# 06_POWER_5.net
KiCad netlist of a schematic drawn in Altium Designer
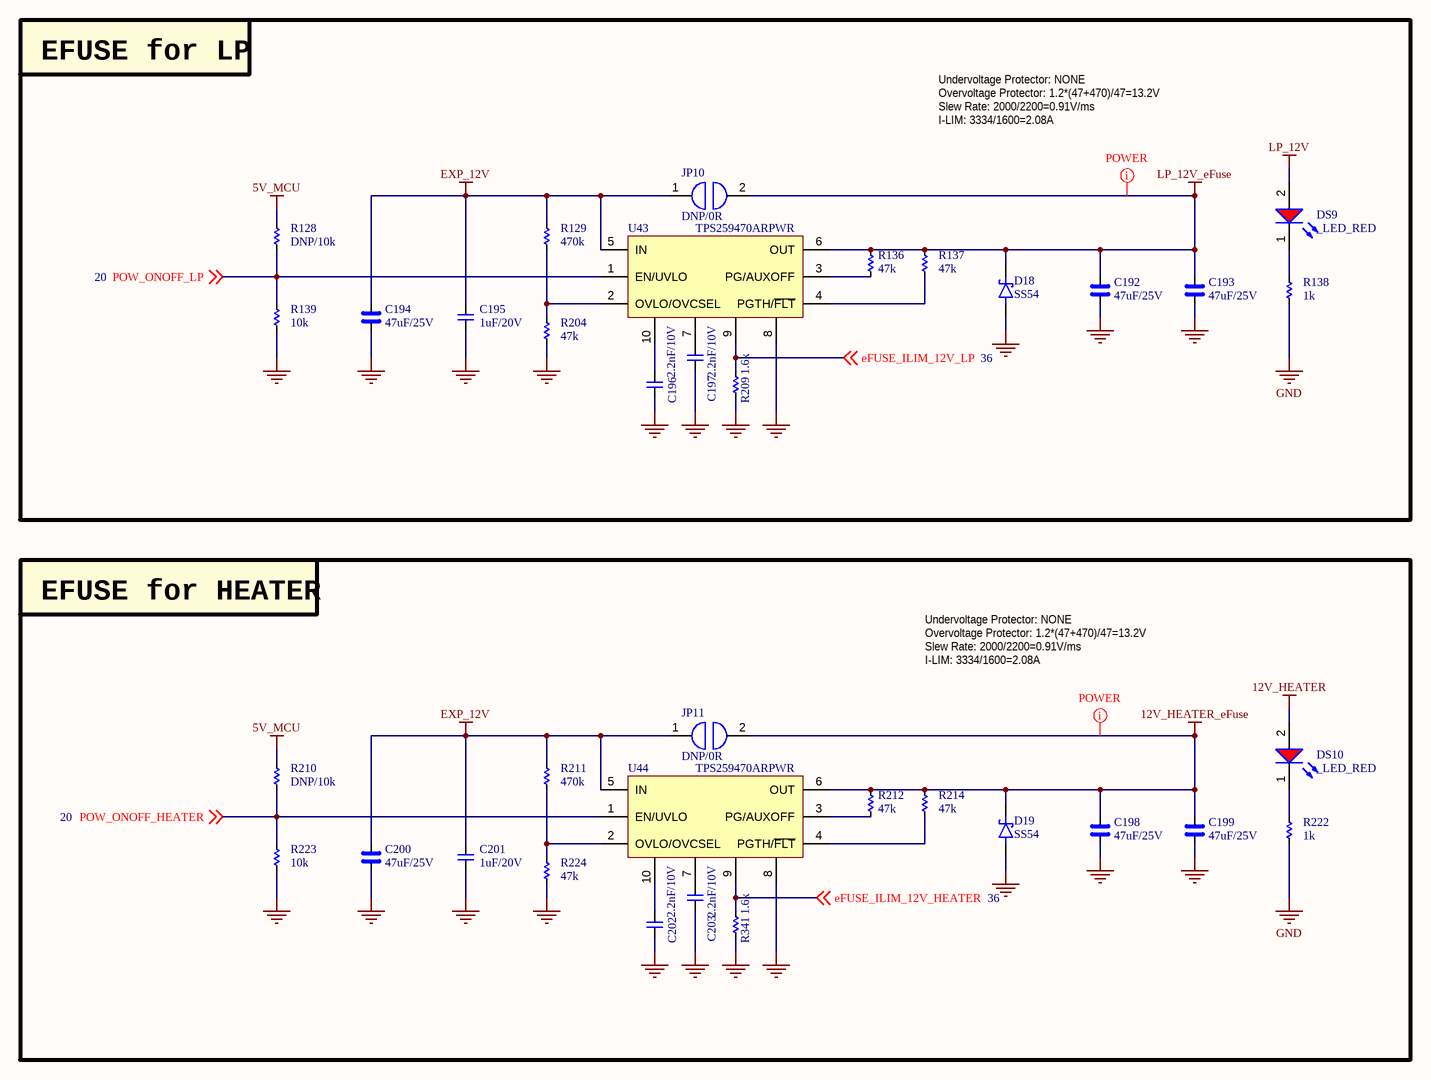
[diagram p0: 06_POWER_5.SchDoc]

(export (version "E")
  (design (tool "Eeschema 10.0.6"))
  (components
    (comp (ref "C192")
      (value "47uF/25V")
      (footprint "CAP_C_3225X80")
      (description "CAP High Value")
      (libsource (lib "LABLIB") (part "_CAP_C_High_2"))
    )
    (comp (ref "C193")
      (value "47uF/25V")
      (footprint "CAP_C_3225X80")
      (description "CAP High Value")
      (libsource (lib "LABLIB") (part "_CAP_C_High_2"))
    )
    (comp (ref "C194")
      (value "47uF/25V")
      (footprint "CAP_C_3225X80")
      (description "CAP High Value")
      (libsource (lib "LABLIB") (part "_CAP_C_High_2"))
    )
    (comp (ref "C195")
      (value "1uF/20V")
      (footprint "CAP_C_1005X60")
      (description "CAP")
      (libsource (lib "LABLIB") (part "_CAP_C_2"))
    )
    (comp (ref "C196")
      (value "2.2nF/10V")
      (footprint "CAP_C_1005X60")
      (description "CAP")
      (libsource (lib "LABLIB") (part "_CAP_C_2"))
    )
    (comp (ref "C197")
      (value "2.2nF/10V")
      (footprint "CAP_C_1005X60")
      (description "CAP")
      (libsource (lib "LABLIB") (part "_CAP_C_2"))
    )
    (comp (ref "C198")
      (value "47uF/25V")
      (footprint "CAP_C_3225X80")
      (description "CAP High Value")
      (libsource (lib "LABLIB") (part "_CAP_C_High_2"))
    )
    (comp (ref "C199")
      (value "47uF/25V")
      (footprint "CAP_C_3225X80")
      (description "CAP High Value")
      (libsource (lib "LABLIB") (part "_CAP_C_High_2"))
    )
    (comp (ref "C200")
      (value "47uF/25V")
      (footprint "CAP_C_3225X80")
      (description "CAP High Value")
      (libsource (lib "LABLIB") (part "_CAP_C_High_2"))
    )
    (comp (ref "C201")
      (value "1uF/20V")
      (footprint "CAP_C_1005X60")
      (description "CAP")
      (libsource (lib "LABLIB") (part "_CAP_C_2"))
    )
    (comp (ref "C202")
      (value "2.2nF/10V")
      (footprint "CAP_C_1005X60")
      (description "CAP")
      (libsource (lib "LABLIB") (part "_CAP_C_2"))
    )
    (comp (ref "C203")
      (value "2.2nF/10V")
      (footprint "CAP_C_1005X60")
      (description "CAP")
      (libsource (lib "LABLIB") (part "_CAP_C_2"))
    )
    (comp (ref "D18")
      (value "SS54")
      (footprint "DO-214AC_SMA")
      (description "DIODE SCHOTTKY")
      (libsource (lib "LABLIB") (part "DIODE SCHOTTKY"))
    )
    (comp (ref "D19")
      (value "SS54")
      (footprint "DO-214AC_SMA")
      (description "DIODE SCHOTTKY")
      (libsource (lib "LABLIB") (part "DIODE SCHOTTKY"))
    )
    (comp (ref "DS9") (value "_LED_RED") (footprint "LED_0603") (libsource (lib "LABLIB") (part "_LED_RED")))
    (comp (ref "DS10") (value "_LED_RED") (footprint "LED_0603") (libsource (lib "LABLIB") (part "_LED_RED")))
    (comp (ref "JP10") (value "DNP/0R") (footprint "JUMPER_1608") (libsource (lib "EXP_V1") (part "JUMPER")))
    (comp (ref "JP11") (value "DNP/0R") (footprint "JUMPER_1608") (libsource (lib "EXP_V1") (part "JUMPER")))
    (comp (ref "R128")
      (value "DNP/10k")
      (footprint "RES_C_1005X40")
      (description "RES")
      (libsource (lib "LABLIB") (part "_RES_B_2"))
    )
    (comp (ref "R129")
      (value "470k")
      (footprint "RES_C_1005X40")
      (description "RES")
      (libsource (lib "LABLIB") (part "_RES_B_2"))
    )
    (comp (ref "R136")
      (value "47k")
      (footprint "RES_C_1005X40")
      (description "RES")
      (libsource (lib "LABLIB") (part "_RES_B_2"))
    )
    (comp (ref "R137")
      (value "47k")
      (footprint "RES_C_1005X40")
      (description "RES")
      (libsource (lib "LABLIB") (part "_RES_B_2"))
    )
    (comp (ref "R138")
      (value "1k")
      (footprint "RES_C_1005X40")
      (description "RES")
      (libsource (lib "LABLIB") (part "_RES_B_2"))
    )
    (comp (ref "R139")
      (value "10k")
      (footprint "RES_C_1005X40")
      (description "RES")
      (libsource (lib "LABLIB") (part "_RES_B_2"))
    )
    (comp (ref "R204")
      (value "47k")
      (footprint "RES_C_1005X40")
      (description "RES")
      (libsource (lib "LABLIB") (part "_RES_B_2"))
    )
    (comp (ref "R209")
      (value "1.6k")
      (footprint "RES_C_1005X40")
      (description "RES")
      (libsource (lib "LABLIB") (part "_RES_B_2"))
    )
    (comp (ref "R210")
      (value "DNP/10k")
      (footprint "RES_C_1005X40")
      (description "RES")
      (libsource (lib "LABLIB") (part "_RES_B_2"))
    )
    (comp (ref "R211")
      (value "470k")
      (footprint "RES_C_1005X40")
      (description "RES")
      (libsource (lib "LABLIB") (part "_RES_B_2"))
    )
    (comp (ref "R212")
      (value "47k")
      (footprint "RES_C_1005X40")
      (description "RES")
      (libsource (lib "LABLIB") (part "_RES_B_2"))
    )
    (comp (ref "R214")
      (value "47k")
      (footprint "RES_C_1005X40")
      (description "RES")
      (libsource (lib "LABLIB") (part "_RES_B_2"))
    )
    (comp (ref "R222")
      (value "1k")
      (footprint "RES_C_1005X40")
      (description "RES")
      (libsource (lib "LABLIB") (part "_RES_B_2"))
    )
    (comp (ref "R223")
      (value "10k")
      (footprint "RES_C_1005X40")
      (description "RES")
      (libsource (lib "LABLIB") (part "_RES_B_2"))
    )
    (comp (ref "R224")
      (value "47k")
      (footprint "RES_C_1005X40")
      (description "RES")
      (libsource (lib "LABLIB") (part "_RES_B_2"))
    )
    (comp (ref "R341")
      (value "1.6k")
      (footprint "RES_C_1005X40")
      (description "RES")
      (libsource (lib "LABLIB") (part "_RES_B_2"))
    )
    (comp (ref "U43")
      (value "TPS259470ARPWR")
      (footprint "VQFN-HR-10")
      (libsource (lib "EXP_HW_V3") (part "TPS259470ARPWR"))
    )
    (comp (ref "U44")
      (value "TPS259470ARPWR")
      (footprint "VQFN-HR-10")
      (libsource (lib "EXP_HW_V3") (part "TPS259470ARPWR"))
    )
  )
  (nets
    (net (code "1") (name "5V_MCU") (class "Default")
      (node (ref "R128") (pin "1") (pinfunction "1_1") (pintype "passive"))
      (node (ref "R210") (pin "1") (pinfunction "1_1") (pintype "passive"))
    )
    (net (code "2") (name "12V_HEATER") (class "Default")
      (node (ref "DS10") (pin "2") (pinfunction "A_2") (pintype "passive"))
    )
    (net (code "3") (name "12V_HEATER_eFuse") (class "Default")
      (node (ref "C198") (pin "2") (pinfunction "2_2") (pintype "passive"))
      (node (ref "C199") (pin "2") (pinfunction "2_2") (pintype "passive"))
      (node (ref "D19") (pin "1") (pinfunction "K_1") (pintype "passive"))
      (node (ref "JP11") (pin "2") (pinfunction "2_2") (pintype "passive"))
      (node (ref "R212") (pin "2") (pinfunction "2_2") (pintype "passive"))
      (node (ref "R214") (pin "2") (pinfunction "2_2") (pintype "passive"))
      (node (ref "U44") (pin "6") (pinfunction "OUT_6") (pintype "passive"))
    )
    (net (code "4") (name "EXP_12V") (class "Default")
      (node (ref "C194") (pin "2") (pinfunction "2_2") (pintype "passive"))
      (node (ref "C195") (pin "2") (pinfunction "2_2") (pintype "passive"))
      (node (ref "C200") (pin "2") (pinfunction "2_2") (pintype "passive"))
      (node (ref "C201") (pin "2") (pinfunction "2_2") (pintype "passive"))
      (node (ref "JP10") (pin "1") (pinfunction "1_1") (pintype "passive"))
      (node (ref "JP11") (pin "1") (pinfunction "1_1") (pintype "passive"))
      (node (ref "R129") (pin "2") (pinfunction "2_2") (pintype "passive"))
      (node (ref "R211") (pin "2") (pinfunction "2_2") (pintype "passive"))
      (node (ref "U43") (pin "5") (pinfunction "IN_5") (pintype "passive"))
      (node (ref "U44") (pin "5") (pinfunction "IN_5") (pintype "passive"))
    )
    (net (code "5") (name "GND") (class "Default")
      (node (ref "C192") (pin "1") (pinfunction "1_1") (pintype "passive"))
      (node (ref "C193") (pin "1") (pinfunction "1_1") (pintype "passive"))
      (node (ref "C194") (pin "1") (pinfunction "1_1") (pintype "passive"))
      (node (ref "C195") (pin "1") (pinfunction "1_1") (pintype "passive"))
      (node (ref "C196") (pin "1") (pinfunction "1_1") (pintype "passive"))
      (node (ref "C197") (pin "1") (pinfunction "1_1") (pintype "passive"))
      (node (ref "C198") (pin "1") (pinfunction "1_1") (pintype "passive"))
      (node (ref "C199") (pin "1") (pinfunction "1_1") (pintype "passive"))
      (node (ref "C200") (pin "1") (pinfunction "1_1") (pintype "passive"))
      (node (ref "C201") (pin "1") (pinfunction "1_1") (pintype "passive"))
      (node (ref "C202") (pin "1") (pinfunction "1_1") (pintype "passive"))
      (node (ref "C203") (pin "1") (pinfunction "1_1") (pintype "passive"))
      (node (ref "D18") (pin "2") (pinfunction "A_2") (pintype "passive"))
      (node (ref "D19") (pin "2") (pinfunction "A_2") (pintype "passive"))
      (node (ref "R138") (pin "1") (pinfunction "1_1") (pintype "passive"))
      (node (ref "R139") (pin "2") (pinfunction "2_2") (pintype "passive"))
      (node (ref "R204") (pin "1") (pinfunction "1_1") (pintype "passive"))
      (node (ref "R209") (pin "1") (pinfunction "1_1") (pintype "passive"))
      (node (ref "R222") (pin "1") (pinfunction "1_1") (pintype "passive"))
      (node (ref "R223") (pin "2") (pinfunction "2_2") (pintype "passive"))
      (node (ref "R224") (pin "1") (pinfunction "1_1") (pintype "passive"))
      (node (ref "R341") (pin "1") (pinfunction "1_1") (pintype "passive"))
      (node (ref "U43") (pin "8") (pinfunction "8_8") (pintype "passive"))
      (node (ref "U44") (pin "8") (pinfunction "8_8") (pintype "passive"))
    )
    (net (code "6") (name "LP_12V") (class "Default")
      (node (ref "DS9") (pin "2") (pinfunction "A_2") (pintype "passive"))
    )
    (net (code "7") (name "LP_12V_eFuse") (class "Default")
      (node (ref "C192") (pin "2") (pinfunction "2_2") (pintype "passive"))
      (node (ref "C193") (pin "2") (pinfunction "2_2") (pintype "passive"))
      (node (ref "D18") (pin "1") (pinfunction "K_1") (pintype "passive"))
      (node (ref "JP10") (pin "2") (pinfunction "2_2") (pintype "passive"))
      (node (ref "R136") (pin "2") (pinfunction "2_2") (pintype "passive"))
      (node (ref "R137") (pin "2") (pinfunction "2_2") (pintype "passive"))
      (node (ref "U43") (pin "6") (pinfunction "OUT_6") (pintype "passive"))
    )
    (net (code "8") (name "Net-(C196-Pad2)") (class "Default")
      (node (ref "C196") (pin "2") (pinfunction "2_2") (pintype "passive"))
      (node (ref "U43") (pin "10") (pinfunction "10_10") (pintype "passive"))
    )
    (net (code "9") (name "Net-(C197-Pad2)") (class "Default")
      (node (ref "C197") (pin "2") (pinfunction "2_2") (pintype "passive"))
      (node (ref "U43") (pin "7") (pinfunction "7_7") (pintype "passive"))
    )
    (net (code "10") (name "Net-(C202-Pad2)") (class "Default")
      (node (ref "C202") (pin "2") (pinfunction "2_2") (pintype "passive"))
      (node (ref "U44") (pin "10") (pinfunction "10_10") (pintype "passive"))
    )
    (net (code "11") (name "Net-(C203-Pad2)") (class "Default")
      (node (ref "C203") (pin "2") (pinfunction "2_2") (pintype "passive"))
      (node (ref "U44") (pin "7") (pinfunction "7_7") (pintype "passive"))
    )
    (net (code "12") (name "Net-(DS9-K)") (class "Default")
      (node (ref "DS9") (pin "1") (pinfunction "K_1") (pintype "passive"))
      (node (ref "R138") (pin "2") (pinfunction "2_2") (pintype "passive"))
    )
    (net (code "13") (name "Net-(DS10-K)") (class "Default")
      (node (ref "DS10") (pin "1") (pinfunction "K_1") (pintype "passive"))
      (node (ref "R222") (pin "2") (pinfunction "2_2") (pintype "passive"))
    )
    (net (code "14") (name "Net-(U43-OVLO{slash}OVCSEL)") (class "Default")
      (node (ref "R129") (pin "1") (pinfunction "1_1") (pintype "passive"))
      (node (ref "R204") (pin "2") (pinfunction "2_2") (pintype "passive"))
      (node (ref "U43") (pin "2") (pinfunction "OVLO/OVCSEL_2") (pintype "passive"))
    )
    (net (code "15") (name "Net-(U43-PGTH{slash}~{FLT})") (class "Default")
      (node (ref "R137") (pin "1") (pinfunction "1_1") (pintype "passive"))
      (node (ref "U43") (pin "4") (pinfunction "PGTH/~{FLT}_4") (pintype "passive"))
    )
    (net (code "16") (name "Net-(U43-PG{slash}AUXOFF)") (class "Default")
      (node (ref "R136") (pin "1") (pinfunction "1_1") (pintype "passive"))
      (node (ref "U43") (pin "3") (pinfunction "PG/AUXOFF_3") (pintype "passive"))
    )
    (net (code "17") (name "Net-(U44-OVLO{slash}OVCSEL)") (class "Default")
      (node (ref "R211") (pin "1") (pinfunction "1_1") (pintype "passive"))
      (node (ref "R224") (pin "2") (pinfunction "2_2") (pintype "passive"))
      (node (ref "U44") (pin "2") (pinfunction "OVLO/OVCSEL_2") (pintype "passive"))
    )
    (net (code "18") (name "Net-(U44-PGTH{slash}~{FLT})") (class "Default")
      (node (ref "R214") (pin "1") (pinfunction "1_1") (pintype "passive"))
      (node (ref "U44") (pin "4") (pinfunction "PGTH/~{FLT}_4") (pintype "passive"))
    )
    (net (code "19") (name "Net-(U44-PG{slash}AUXOFF)") (class "Default")
      (node (ref "R212") (pin "1") (pinfunction "1_1") (pintype "passive"))
      (node (ref "U44") (pin "3") (pinfunction "PG/AUXOFF_3") (pintype "passive"))
    )
    (net (code "20") (name "POW_ONOFF_HEATER") (class "Default")
      (node (ref "R210") (pin "2") (pinfunction "2_2") (pintype "passive"))
      (node (ref "R223") (pin "1") (pinfunction "1_1") (pintype "passive"))
      (node (ref "U44") (pin "1") (pinfunction "EN/UVLO_1") (pintype "passive"))
    )
    (net (code "21") (name "POW_ONOFF_LP") (class "Default")
      (node (ref "R128") (pin "2") (pinfunction "2_2") (pintype "passive"))
      (node (ref "R139") (pin "1") (pinfunction "1_1") (pintype "passive"))
      (node (ref "U43") (pin "1") (pinfunction "EN/UVLO_1") (pintype "passive"))
    )
    (net (code "22") (name "eFUSE_ILIM_12V_HEATER") (class "Default")
      (node (ref "R341") (pin "2") (pinfunction "2_2") (pintype "passive"))
      (node (ref "U44") (pin "9") (pinfunction "9_9") (pintype "passive"))
    )
    (net (code "23") (name "eFUSE_ILIM_12V_LP") (class "Default")
      (node (ref "R209") (pin "2") (pinfunction "2_2") (pintype "passive"))
      (node (ref "U43") (pin "9") (pinfunction "9_9") (pintype "passive"))
    )
  )
)
